# microcontroller.net
KiCad netlist of a schematic drawn in Altium Designer
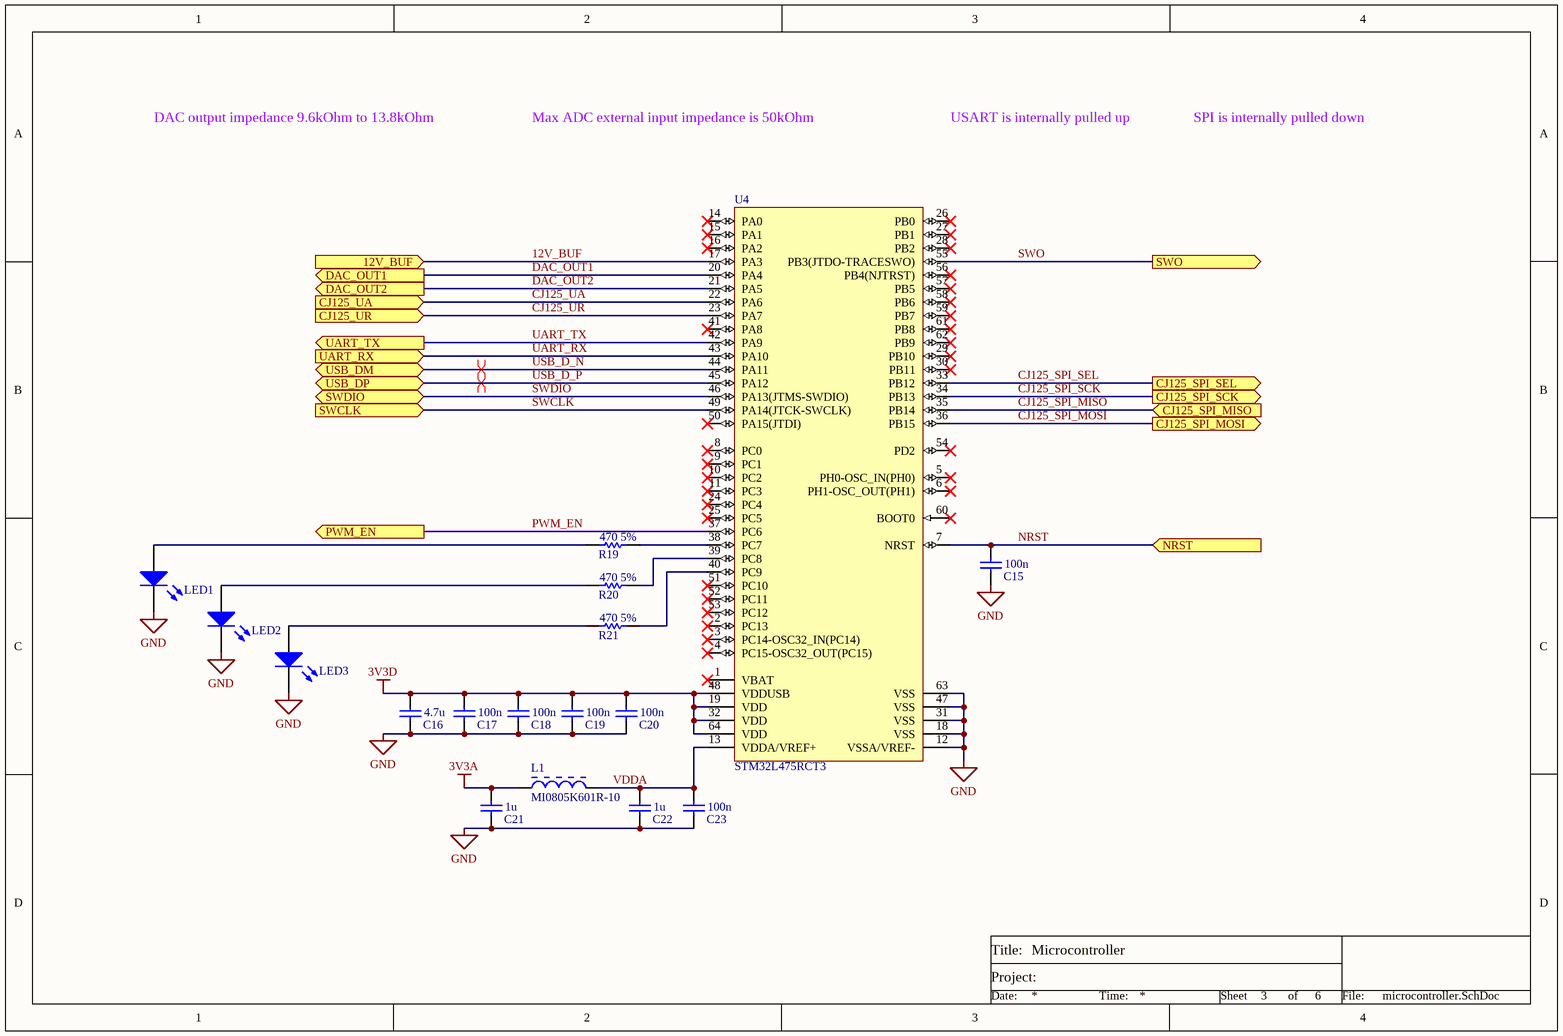
[diagram p0: microcontroller.SchDoc]

(export (version "E")
  (design (tool "Eeschema 10.0.6"))
  (components
    (comp (ref "C15")
      (value "100n")
      (footprint "0805")
      (description "Generic 0805 Capacitor")
      (libsource (lib "symbol_library") (part "C_0805"))
    )
    (comp (ref "C16")
      (value "4.7u")
      (footprint "0805")
      (description "Generic 0805 Capacitor")
      (libsource (lib "symbol_library") (part "C_0805"))
    )
    (comp (ref "C17")
      (value "100n")
      (footprint "0805")
      (description "Generic 0805 Capacitor")
      (libsource (lib "symbol_library") (part "C_0805"))
    )
    (comp (ref "C18")
      (value "100n")
      (footprint "0805")
      (description "Generic 0805 Capacitor")
      (libsource (lib "symbol_library") (part "C_0805"))
    )
    (comp (ref "C19")
      (value "100n")
      (footprint "0805")
      (description "Generic 0805 Capacitor")
      (libsource (lib "symbol_library") (part "C_0805"))
    )
    (comp (ref "C20")
      (value "100n")
      (footprint "0805")
      (description "Generic 0805 Capacitor")
      (libsource (lib "symbol_library") (part "C_0805"))
    )
    (comp (ref "C21")
      (value "1u")
      (footprint "0805")
      (description "Generic 0805 Capacitor")
      (libsource (lib "symbol_library") (part "C_0805"))
    )
    (comp (ref "C22")
      (value "1u")
      (footprint "0805")
      (description "Generic 0805 Capacitor")
      (libsource (lib "symbol_library") (part "C_0805"))
    )
    (comp (ref "C23")
      (value "100n")
      (footprint "0805")
      (description "Generic 0805 Capacitor")
      (libsource (lib "symbol_library") (part "C_0805"))
    )
    (comp (ref "L1")
      (value "MI0805K601R-10")
      (footprint "0805")
      (fields (field (name "MANUFACTURER") "Laird"))
      (libsource (lib "symbol_library") (part "MI0805K"))
    )
    (comp (ref "LED1")
      (value "150080SS75000")
      (footprint "0805_A")
      (description "SMD mono-color Chip LED, WL-SMCW, Super Red")
      (fields (field (name "MANUFACTURER") "Wuerth Elektronik"))
      (libsource (lib "symbol_library") (part "LED_0805"))
    )
    (comp (ref "LED2")
      (value "150080SS75000")
      (footprint "0805_A")
      (description "SMD mono-color Chip LED, WL-SMCW, Super Red")
      (fields (field (name "MANUFACTURER") "Wuerth Elektronik"))
      (libsource (lib "symbol_library") (part "LED_0805"))
    )
    (comp (ref "LED3")
      (value "150080SS75000")
      (footprint "0805_A")
      (description "SMD mono-color Chip LED, WL-SMCW, Super Red")
      (fields (field (name "MANUFACTURER") "Wuerth Elektronik"))
      (libsource (lib "symbol_library") (part "LED_0805"))
    )
    (comp (ref "R19")
      (value "470 5%")
      (footprint "0603")
      (description "Generic 0603 Resistor")
      (libsource (lib "symbol_library") (part "R_0603"))
    )
    (comp (ref "R20")
      (value "470 5%")
      (footprint "0603")
      (description "Generic 0603 Resistor")
      (libsource (lib "symbol_library") (part "R_0603"))
    )
    (comp (ref "R21")
      (value "470 5%")
      (footprint "0603")
      (description "Generic 0603 Resistor")
      (libsource (lib "symbol_library") (part "R_0603"))
    )
    (comp (ref "U4")
      (value "STM32L475RCT3")
      (footprint "STM-LQFP64_L")
      (libsource (lib "symbol_library") (part "STM32L475RCT3"))
    )
  )
  (nets
    (net (code "1") (name "/12V_BUF") (class "Default")
      (node (ref "U4") (pin "17") (pinfunction "PA3_17") (pintype "bidirectional"))
    )
    (net (code "2") (name "/CJ125_SPI_MISO") (class "Default")
      (node (ref "U4") (pin "35") (pinfunction "PB14_35") (pintype "bidirectional"))
    )
    (net (code "3") (name "/CJ125_SPI_MOSI") (class "Default")
      (node (ref "U4") (pin "36") (pinfunction "PB15_36") (pintype "bidirectional"))
    )
    (net (code "4") (name "/CJ125_SPI_SCK") (class "Default")
      (node (ref "U4") (pin "34") (pinfunction "PB13_34") (pintype "bidirectional"))
    )
    (net (code "5") (name "/CJ125_SPI_SEL") (class "Default")
      (node (ref "U4") (pin "33") (pinfunction "PB12_33") (pintype "bidirectional"))
    )
    (net (code "6") (name "/CJ125_UA") (class "Default")
      (node (ref "U4") (pin "22") (pinfunction "PA6_22") (pintype "bidirectional"))
    )
    (net (code "7") (name "/CJ125_UR") (class "Default")
      (node (ref "U4") (pin "23") (pinfunction "PA7_23") (pintype "bidirectional"))
    )
    (net (code "8") (name "/DAC_OUT1") (class "Default")
      (node (ref "U4") (pin "20") (pinfunction "PA4_20") (pintype "bidirectional"))
    )
    (net (code "9") (name "/DAC_OUT2") (class "Default")
      (node (ref "U4") (pin "21") (pinfunction "PA5_21") (pintype "bidirectional"))
    )
    (net (code "10") (name "/NRST") (class "Default")
      (node (ref "C15") (pin "2") (pinfunction "2_2") (pintype "passive"))
      (node (ref "U4") (pin "7") (pinfunction "NRST_7") (pintype "bidirectional"))
    )
    (net (code "11") (name "/PWM_EN") (class "Default")
      (node (ref "U4") (pin "37") (pinfunction "PC6_37") (pintype "bidirectional"))
    )
    (net (code "12") (name "/SWCLK") (class "Default")
      (node (ref "U4") (pin "49") (pinfunction "PA14(JTCK-SWCLK)_49") (pintype "bidirectional"))
    )
    (net (code "13") (name "/SWDIO") (class "Default")
      (node (ref "U4") (pin "46") (pinfunction "PA13(JTMS-SWDIO)_46") (pintype "bidirectional"))
    )
    (net (code "14") (name "/SWO") (class "Default")
      (node (ref "U4") (pin "55") (pinfunction "PB3(JTDO-TRACESWO)_55") (pintype "bidirectional"))
    )
    (net (code "15") (name "/UART_RX") (class "Default")
      (node (ref "U4") (pin "43") (pinfunction "PA10_43") (pintype "bidirectional"))
    )
    (net (code "16") (name "/UART_TX") (class "Default")
      (node (ref "U4") (pin "42") (pinfunction "PA9_42") (pintype "bidirectional"))
    )
    (net (code "17") (name "/USB_D_N") (class "Default")
      (node (ref "U4") (pin "44") (pinfunction "PA11_44") (pintype "bidirectional"))
    )
    (net (code "18") (name "/USB_D_P") (class "Default")
      (node (ref "U4") (pin "45") (pinfunction "PA12_45") (pintype "bidirectional"))
    )
    (net (code "19") (name "/VDDA") (class "Default")
      (node (ref "C22") (pin "2") (pinfunction "2_2") (pintype "passive"))
      (node (ref "C23") (pin "2") (pinfunction "2_2") (pintype "passive"))
      (node (ref "L1") (pin "2") (pinfunction "2_2") (pintype "passive"))
      (node (ref "U4") (pin "13") (pinfunction "VDDA/VREF+_13") (pintype "power_in"))
    )
    (net (code "20") (name "3V3A") (class "Default")
      (node (ref "C21") (pin "2") (pinfunction "2_2") (pintype "passive"))
      (node (ref "L1") (pin "1") (pinfunction "1_1") (pintype "passive"))
    )
    (net (code "21") (name "3V3D") (class "Default")
      (node (ref "C16") (pin "2") (pinfunction "2_2") (pintype "passive"))
      (node (ref "C17") (pin "2") (pinfunction "2_2") (pintype "passive"))
      (node (ref "C18") (pin "2") (pinfunction "2_2") (pintype "passive"))
      (node (ref "C19") (pin "2") (pinfunction "2_2") (pintype "passive"))
      (node (ref "C20") (pin "2") (pinfunction "2_2") (pintype "passive"))
      (node (ref "U4") (pin "19") (pinfunction "VDD_19") (pintype "power_in"))
      (node (ref "U4") (pin "32") (pinfunction "VDD_32") (pintype "power_in"))
      (node (ref "U4") (pin "48") (pinfunction "VDDUSB_48") (pintype "power_in"))
      (node (ref "U4") (pin "64") (pinfunction "VDD_64") (pintype "power_in"))
    )
    (net (code "22") (name "GND") (class "Default")
      (node (ref "C15") (pin "1") (pinfunction "1_1") (pintype "passive"))
      (node (ref "C16") (pin "1") (pinfunction "1_1") (pintype "passive"))
      (node (ref "C17") (pin "1") (pinfunction "1_1") (pintype "passive"))
      (node (ref "C18") (pin "1") (pinfunction "1_1") (pintype "passive"))
      (node (ref "C19") (pin "1") (pinfunction "1_1") (pintype "passive"))
      (node (ref "C20") (pin "1") (pinfunction "1_1") (pintype "passive"))
      (node (ref "C21") (pin "1") (pinfunction "1_1") (pintype "passive"))
      (node (ref "C22") (pin "1") (pinfunction "1_1") (pintype "passive"))
      (node (ref "C23") (pin "1") (pinfunction "1_1") (pintype "passive"))
      (node (ref "LED1") (pin "1") (pinfunction "K_1") (pintype "passive"))
      (node (ref "LED2") (pin "1") (pinfunction "K_1") (pintype "passive"))
      (node (ref "LED3") (pin "1") (pinfunction "K_1") (pintype "passive"))
      (node (ref "U4") (pin "12") (pinfunction "VSSA/VREF-_12") (pintype "power_in"))
      (node (ref "U4") (pin "18") (pinfunction "VSS_18") (pintype "power_in"))
      (node (ref "U4") (pin "31") (pinfunction "VSS_31") (pintype "power_in"))
      (node (ref "U4") (pin "47") (pinfunction "VSS_47") (pintype "power_in"))
      (node (ref "U4") (pin "63") (pinfunction "VSS_63") (pintype "power_in"))
    )
    (net (code "23") (name "Net-(LED1-A)") (class "Default")
      (node (ref "LED1") (pin "2") (pinfunction "A_2") (pintype "passive"))
      (node (ref "R19") (pin "1") (pinfunction "1_1") (pintype "passive"))
    )
    (net (code "24") (name "Net-(LED2-A)") (class "Default")
      (node (ref "LED2") (pin "2") (pinfunction "A_2") (pintype "passive"))
      (node (ref "R20") (pin "1") (pinfunction "1_1") (pintype "passive"))
    )
    (net (code "25") (name "Net-(LED3-A)") (class "Default")
      (node (ref "LED3") (pin "2") (pinfunction "A_2") (pintype "passive"))
      (node (ref "R21") (pin "1") (pinfunction "1_1") (pintype "passive"))
    )
    (net (code "26") (name "Net-(U4-PC7)") (class "Default")
      (node (ref "R19") (pin "2") (pinfunction "2_2") (pintype "passive"))
      (node (ref "U4") (pin "38") (pinfunction "PC7_38") (pintype "bidirectional"))
    )
    (net (code "27") (name "Net-(U4-PC8)") (class "Default")
      (node (ref "R20") (pin "2") (pinfunction "2_2") (pintype "passive"))
      (node (ref "U4") (pin "39") (pinfunction "PC8_39") (pintype "bidirectional"))
    )
    (net (code "28") (name "Net-(U4-PC9)") (class "Default")
      (node (ref "R21") (pin "2") (pinfunction "2_2") (pintype "passive"))
      (node (ref "U4") (pin "40") (pinfunction "PC9_40") (pintype "bidirectional"))
    )
    (net (code "29") (name "unconnected-(U4-BOOT0-Pad60)") (class "Default")
      (node (ref "U4") (pin "60") (pinfunction "BOOT0_60") (pintype "input+no_connect"))
    )
    (net (code "30") (name "unconnected-(U4-PA0-Pad14)") (class "Default")
      (node (ref "U4") (pin "14") (pinfunction "PA0_14") (pintype "bidirectional+no_connect"))
    )
    (net (code "31") (name "unconnected-(U4-PA1-Pad15)") (class "Default")
      (node (ref "U4") (pin "15") (pinfunction "PA1_15") (pintype "bidirectional+no_connect"))
    )
    (net (code "32") (name "unconnected-(U4-PA2-Pad16)") (class "Default")
      (node (ref "U4") (pin "16") (pinfunction "PA2_16") (pintype "bidirectional+no_connect"))
    )
    (net (code "33") (name "unconnected-(U4-PA8-Pad41)") (class "Default")
      (node (ref "U4") (pin "41") (pinfunction "PA8_41") (pintype "bidirectional+no_connect"))
    )
    (net (code "34") (name "unconnected-(U4-PA15(JTDI)-Pad50)") (class "Default")
      (node (ref "U4") (pin "50") (pinfunction "PA15(JTDI)_50") (pintype "bidirectional+no_connect"))
    )
    (net (code "35") (name "unconnected-(U4-PB0-Pad26)") (class "Default")
      (node (ref "U4") (pin "26") (pinfunction "PB0_26") (pintype "bidirectional+no_connect"))
    )
    (net (code "36") (name "unconnected-(U4-PB1-Pad27)") (class "Default")
      (node (ref "U4") (pin "27") (pinfunction "PB1_27") (pintype "bidirectional+no_connect"))
    )
    (net (code "37") (name "unconnected-(U4-PB2-Pad28)") (class "Default")
      (node (ref "U4") (pin "28") (pinfunction "PB2_28") (pintype "bidirectional+no_connect"))
    )
    (net (code "38") (name "unconnected-(U4-PB4(NJTRST)-Pad56)") (class "Default")
      (node (ref "U4") (pin "56") (pinfunction "PB4(NJTRST)_56") (pintype "bidirectional+no_connect"))
    )
    (net (code "39") (name "unconnected-(U4-PB5-Pad57)") (class "Default")
      (node (ref "U4") (pin "57") (pinfunction "PB5_57") (pintype "bidirectional+no_connect"))
    )
    (net (code "40") (name "unconnected-(U4-PB6-Pad58)") (class "Default")
      (node (ref "U4") (pin "58") (pinfunction "PB6_58") (pintype "bidirectional+no_connect"))
    )
    (net (code "41") (name "unconnected-(U4-PB7-Pad59)") (class "Default")
      (node (ref "U4") (pin "59") (pinfunction "PB7_59") (pintype "bidirectional+no_connect"))
    )
    (net (code "42") (name "unconnected-(U4-PB8-Pad61)") (class "Default")
      (node (ref "U4") (pin "61") (pinfunction "PB8_61") (pintype "bidirectional+no_connect"))
    )
    (net (code "43") (name "unconnected-(U4-PB9-Pad62)") (class "Default")
      (node (ref "U4") (pin "62") (pinfunction "PB9_62") (pintype "bidirectional+no_connect"))
    )
    (net (code "44") (name "unconnected-(U4-PB10-Pad29)") (class "Default")
      (node (ref "U4") (pin "29") (pinfunction "PB10_29") (pintype "bidirectional+no_connect"))
    )
    (net (code "45") (name "unconnected-(U4-PB11-Pad30)") (class "Default")
      (node (ref "U4") (pin "30") (pinfunction "PB11_30") (pintype "bidirectional+no_connect"))
    )
    (net (code "46") (name "unconnected-(U4-PC0-Pad8)") (class "Default")
      (node (ref "U4") (pin "8") (pinfunction "PC0_8") (pintype "bidirectional+no_connect"))
    )
    (net (code "47") (name "unconnected-(U4-PC1-Pad9)") (class "Default")
      (node (ref "U4") (pin "9") (pinfunction "PC1_9") (pintype "bidirectional+no_connect"))
    )
    (net (code "48") (name "unconnected-(U4-PC2-Pad10)") (class "Default")
      (node (ref "U4") (pin "10") (pinfunction "PC2_10") (pintype "bidirectional+no_connect"))
    )
    (net (code "49") (name "unconnected-(U4-PC3-Pad11)") (class "Default")
      (node (ref "U4") (pin "11") (pinfunction "PC3_11") (pintype "bidirectional+no_connect"))
    )
    (net (code "50") (name "unconnected-(U4-PC4-Pad24)") (class "Default")
      (node (ref "U4") (pin "24") (pinfunction "PC4_24") (pintype "bidirectional+no_connect"))
    )
    (net (code "51") (name "unconnected-(U4-PC5-Pad25)") (class "Default")
      (node (ref "U4") (pin "25") (pinfunction "PC5_25") (pintype "bidirectional+no_connect"))
    )
    (net (code "52") (name "unconnected-(U4-PC10-Pad51)") (class "Default")
      (node (ref "U4") (pin "51") (pinfunction "PC10_51") (pintype "bidirectional+no_connect"))
    )
    (net (code "53") (name "unconnected-(U4-PC11-Pad52)") (class "Default")
      (node (ref "U4") (pin "52") (pinfunction "PC11_52") (pintype "bidirectional+no_connect"))
    )
    (net (code "54") (name "unconnected-(U4-PC12-Pad53)") (class "Default")
      (node (ref "U4") (pin "53") (pinfunction "PC12_53") (pintype "bidirectional+no_connect"))
    )
    (net (code "55") (name "unconnected-(U4-PC13-Pad2)") (class "Default")
      (node (ref "U4") (pin "2") (pinfunction "PC13_2") (pintype "bidirectional+no_connect"))
    )
    (net (code "56") (name "unconnected-(U4-PC14-OSC32_IN(PC14)-Pad3)") (class "Default")
      (node (ref "U4") (pin "3") (pinfunction "PC14-OSC32_IN(PC14)_3") (pintype "bidirectional+no_connect"))
    )
    (net (code "57") (name "unconnected-(U4-PC15-OSC32_OUT(PC15)-Pad4)") (class "Default")
      (node (ref "U4") (pin "4") (pinfunction "PC15-OSC32_OUT(PC15)_4") (pintype "bidirectional+no_connect"))
    )
    (net (code "58") (name "unconnected-(U4-PD2-Pad54)") (class "Default")
      (node (ref "U4") (pin "54") (pinfunction "PD2_54") (pintype "bidirectional+no_connect"))
    )
    (net (code "59") (name "unconnected-(U4-PH0-OSC_IN(PH0)-Pad5)") (class "Default")
      (node (ref "U4") (pin "5") (pinfunction "PH0-OSC_IN(PH0)_5") (pintype "bidirectional+no_connect"))
    )
    (net (code "60") (name "unconnected-(U4-PH1-OSC_OUT(PH1)-Pad6)") (class "Default")
      (node (ref "U4") (pin "6") (pinfunction "PH1-OSC_OUT(PH1)_6") (pintype "bidirectional+no_connect"))
    )
    (net (code "61") (name "unconnected-(U4-VBAT-Pad1)") (class "Default")
      (node (ref "U4") (pin "1") (pinfunction "VBAT_1") (pintype "power_in+no_connect"))
    )
  )
)
